# LightingSensor.net
KiCad netlist of a schematic drawn in Altium Designer
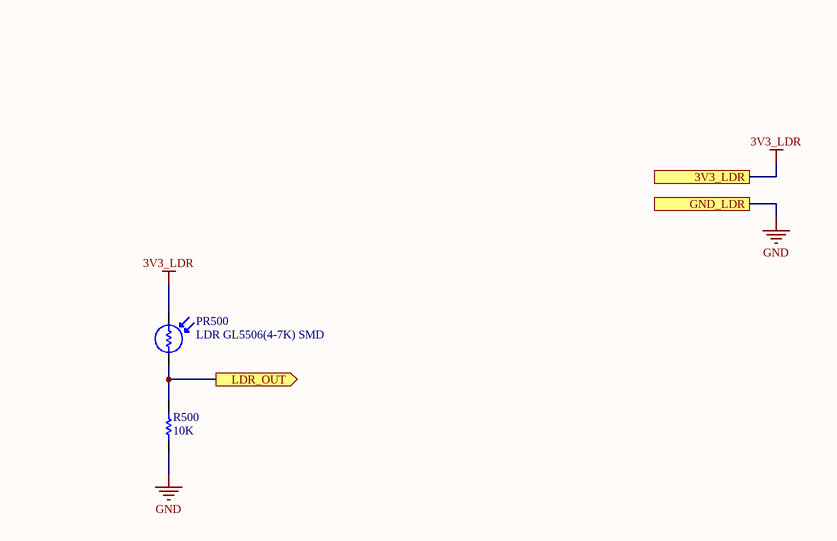
[diagram p0: LightingSensor.SchDoc]

(export (version "E")
  (design (tool "Eeschema 10.0.6"))
  (components
    (comp (ref "PR500")
      (value "LDR GL5506(4-7K) SMD")
      (footprint "LDR 3x0.5")
      (description "THROUGH HOLE PHOTORESISTORS ROHS")
      (fields (field (name "SOURCE") "mits.SchLib"))
      (libsource (lib "Mobit Brasil Ltda") (part "LDR GL5506(4-7K) SMD"))
    )
    (comp (ref "R500")
      (value "10K")
      (footprint "CR2012-0805")
      (description "RES 0805 10K Ohm 0.1% 1/10W  SMD")
      (fields
        (field (name "MANUFACTURER PART NUMBER") "ERJ-6ENF1002V")
        (field (name "MANUFACTURER") "Panasonic Electronic Components")
        (field (name "SOURCE") "mits.SchLib")
      )
      (libsource (lib "Mobit Brasil Ltda") (part "Symbol"))
    )
  )
  (nets
    (net (code "1") (name "/LDR_OUT") (class "Default")
      (node (ref "PR500") (pin "2") (pinfunction "2_2") (pintype "passive"))
      (node (ref "R500") (pin "2") (pinfunction "2_2") (pintype "passive"))
    )
    (net (code "2") (name "3V3_LDR") (class "Default")
      (node (ref "PR500") (pin "1") (pinfunction "1_1") (pintype "passive"))
    )
    (net (code "3") (name "GND") (class "Default")
      (node (ref "R500") (pin "1") (pinfunction "1_1") (pintype "passive"))
    )
  )
)
